# Respirador_Motor.net
KiCad netlist of a schematic drawn in EAGLE
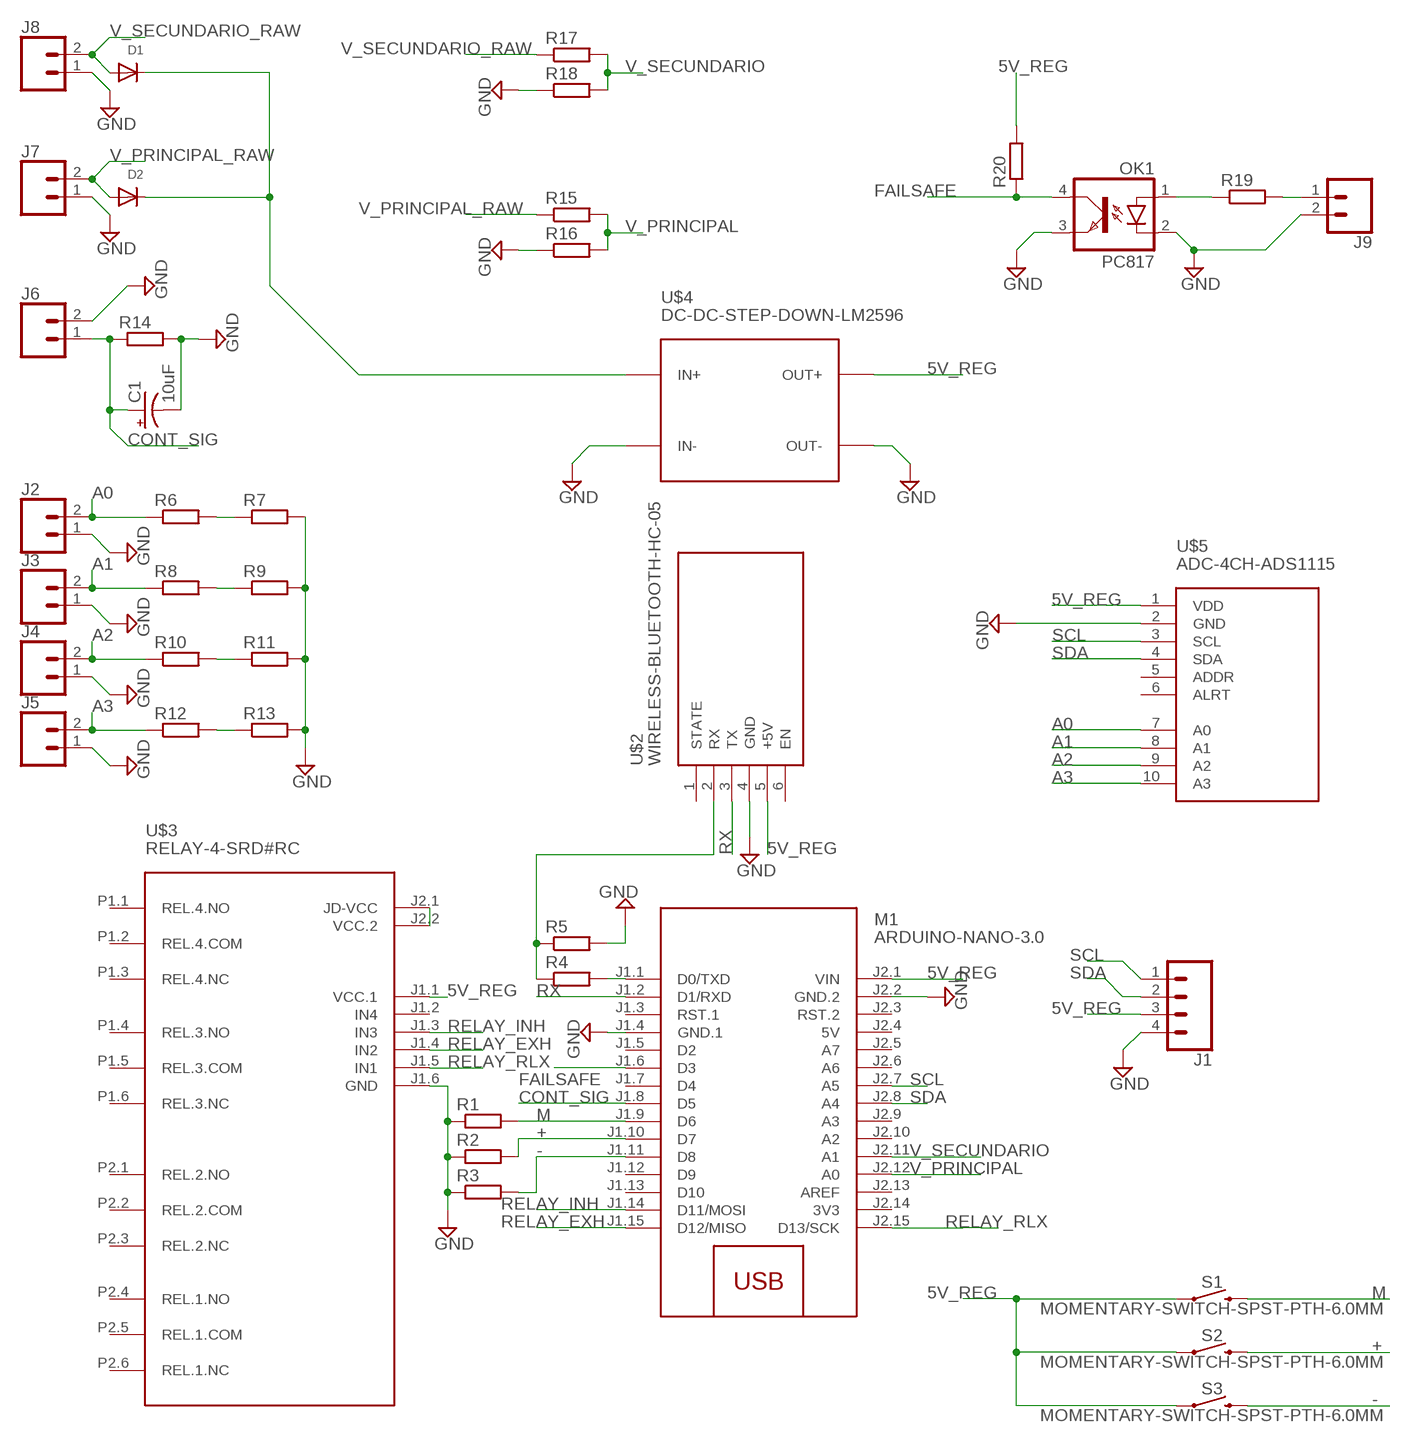
[diagram p0: schematic, sheet 1]

(export (version "E")
  (design (tool "Eeschema 10.0.6"))
  (components
    (comp (ref "C1")
      (value "10uF")
      (footprint "eagle-import:EIA3216")
      (libsource (lib "eagle-import") (part "10UF-TANT"))
    )
    (comp (ref "D1")
      (value "DIODEDO-1N4148")
      (footprint "eagle-import:DO-1N4148")
      (libsource (lib "eagle-import") (part "DIODEDO-1N4148"))
    )
    (comp (ref "D2")
      (value "DIODEDO-1N4148")
      (footprint "eagle-import:DO-1N4148")
      (libsource (lib "eagle-import") (part "DIODEDO-1N4148"))
    )
    (comp (ref "J1")
      (value "CONN_04")
      (footprint "eagle-import:1X04")
      (libsource (lib "eagle-import") (part "CONN_04"))
    )
    (comp (ref "J2")
      (value "CONN_025MM")
      (footprint "eagle-import:SCREWTERMINAL-5MM-2")
      (libsource (lib "eagle-import") (part "CONN_025MM"))
    )
    (comp (ref "J3")
      (value "CONN_025MM")
      (footprint "eagle-import:SCREWTERMINAL-5MM-2")
      (libsource (lib "eagle-import") (part "CONN_025MM"))
    )
    (comp (ref "J4")
      (value "CONN_025MM")
      (footprint "eagle-import:SCREWTERMINAL-5MM-2")
      (libsource (lib "eagle-import") (part "CONN_025MM"))
    )
    (comp (ref "J5")
      (value "CONN_025MM")
      (footprint "eagle-import:SCREWTERMINAL-5MM-2")
      (libsource (lib "eagle-import") (part "CONN_025MM"))
    )
    (comp (ref "J6")
      (value "CONN_025MM")
      (footprint "eagle-import:SCREWTERMINAL-5MM-2")
      (libsource (lib "eagle-import") (part "CONN_025MM"))
    )
    (comp (ref "J7")
      (value "CONN_025MM")
      (footprint "eagle-import:SCREWTERMINAL-5MM-2")
      (libsource (lib "eagle-import") (part "CONN_025MM"))
    )
    (comp (ref "J8")
      (value "CONN_025MM")
      (footprint "eagle-import:SCREWTERMINAL-5MM-2")
      (libsource (lib "eagle-import") (part "CONN_025MM"))
    )
    (comp (ref "J9")
      (value "CONN_025MM")
      (footprint "eagle-import:SCREWTERMINAL-5MM-2")
      (libsource (lib "eagle-import") (part "CONN_025MM"))
    )
    (comp (ref "M1")
      (value "ARDUINO-NANO-3.0")
      (footprint "eagle-import:ARDUINO-NANO-3.0")
      (libsource (lib "eagle-import") (part "ARDUINO-NANO-3.0"))
    )
    (comp (ref "OK1")
      (value "PC817")
      (footprint "eagle-import:DIL04")
      (fields (field (name "MPN") "PC817X4J000F"))
      (libsource (lib "eagle-import") (part "PC817"))
    )
    (comp (ref "R1")
      (value "R-EU_0207/10")
      (footprint "eagle-import:0207_10")
      (libsource (lib "eagle-import") (part "R-EU_0207/10"))
    )
    (comp (ref "R2")
      (value "R-EU_0207/10")
      (footprint "eagle-import:0207_10")
      (libsource (lib "eagle-import") (part "R-EU_0207/10"))
    )
    (comp (ref "R3")
      (value "R-EU_0207/10")
      (footprint "eagle-import:0207_10")
      (libsource (lib "eagle-import") (part "R-EU_0207/10"))
    )
    (comp (ref "R4")
      (value "R-EU_0207/10")
      (footprint "eagle-import:0207_10")
      (libsource (lib "eagle-import") (part "R-EU_0207/10"))
    )
    (comp (ref "R5")
      (value "R-EU_0207/10")
      (footprint "eagle-import:0207_10")
      (libsource (lib "eagle-import") (part "R-EU_0207/10"))
    )
    (comp (ref "R6")
      (value "R-EU_0207/10")
      (footprint "eagle-import:0207_10")
      (libsource (lib "eagle-import") (part "R-EU_0207/10"))
    )
    (comp (ref "R7")
      (value "R-EU_0207/10")
      (footprint "eagle-import:0207_10")
      (libsource (lib "eagle-import") (part "R-EU_0207/10"))
    )
    (comp (ref "R8")
      (value "R-EU_0207/10")
      (footprint "eagle-import:0207_10")
      (libsource (lib "eagle-import") (part "R-EU_0207/10"))
    )
    (comp (ref "R9")
      (value "R-EU_0207/10")
      (footprint "eagle-import:0207_10")
      (libsource (lib "eagle-import") (part "R-EU_0207/10"))
    )
    (comp (ref "R10")
      (value "R-EU_0207/10")
      (footprint "eagle-import:0207_10")
      (libsource (lib "eagle-import") (part "R-EU_0207/10"))
    )
    (comp (ref "R11")
      (value "R-EU_0207/10")
      (footprint "eagle-import:0207_10")
      (libsource (lib "eagle-import") (part "R-EU_0207/10"))
    )
    (comp (ref "R12")
      (value "R-EU_0207/10")
      (footprint "eagle-import:0207_10")
      (libsource (lib "eagle-import") (part "R-EU_0207/10"))
    )
    (comp (ref "R13")
      (value "R-EU_0207/10")
      (footprint "eagle-import:0207_10")
      (libsource (lib "eagle-import") (part "R-EU_0207/10"))
    )
    (comp (ref "R14")
      (value "R-EU_0207/10")
      (footprint "eagle-import:0207_10")
      (libsource (lib "eagle-import") (part "R-EU_0207/10"))
    )
    (comp (ref "R15")
      (value "R-EU_0207/10")
      (footprint "eagle-import:0207_10")
      (libsource (lib "eagle-import") (part "R-EU_0207/10"))
    )
    (comp (ref "R16")
      (value "R-EU_0207/10")
      (footprint "eagle-import:0207_10")
      (libsource (lib "eagle-import") (part "R-EU_0207/10"))
    )
    (comp (ref "R17")
      (value "R-EU_0207/10")
      (footprint "eagle-import:0207_10")
      (libsource (lib "eagle-import") (part "R-EU_0207/10"))
    )
    (comp (ref "R18")
      (value "R-EU_0207/10")
      (footprint "eagle-import:0207_10")
      (libsource (lib "eagle-import") (part "R-EU_0207/10"))
    )
    (comp (ref "R19")
      (value "R-EU_0207/10")
      (footprint "eagle-import:0207_10")
      (libsource (lib "eagle-import") (part "R-EU_0207/10"))
    )
    (comp (ref "R20")
      (value "R-EU_0207/10")
      (footprint "eagle-import:0207_10")
      (libsource (lib "eagle-import") (part "R-EU_0207/10"))
    )
    (comp (ref "S1")
      (value "MOMENTARY-SWITCH-SPST-PTH-6.0MM")
      (footprint "eagle-import:TACTILE_SWITCH_PTH_6.0MM")
      (libsource (lib "eagle-import") (part "MOMENTARY-SWITCH-SPST-PTH-6.0MM"))
    )
    (comp (ref "S2")
      (value "MOMENTARY-SWITCH-SPST-PTH-6.0MM")
      (footprint "eagle-import:TACTILE_SWITCH_PTH_6.0MM")
      (libsource (lib "eagle-import") (part "MOMENTARY-SWITCH-SPST-PTH-6.0MM"))
    )
    (comp (ref "S3")
      (value "MOMENTARY-SWITCH-SPST-PTH-6.0MM")
      (footprint "eagle-import:TACTILE_SWITCH_PTH_6.0MM")
      (libsource (lib "eagle-import") (part "MOMENTARY-SWITCH-SPST-PTH-6.0MM"))
    )
    (comp (ref "U$2")
      (value "WIRELESS-BLUETOOTH-HC-05")
      (footprint "eagle-import:WIRELESS-BLUETOOTH-HC-05")
      (libsource (lib "eagle-import") (part "WIRELESS-BLUETOOTH-HC-05"))
    )
    (comp (ref "U$3")
      (value "RELAY-4-SRD#RC")
      (footprint "eagle-import:RELAY-4-SRD#RC")
      (libsource (lib "eagle-import") (part "RELAY-4-SRD#RC"))
    )
    (comp (ref "U$4")
      (value "DC-DC-STEP-DOWN-LM2596")
      (footprint "eagle-import:DC-DC-STEP-DOWN-LM2596")
      (libsource (lib "eagle-import") (part "DC-DC-STEP-DOWN-LM2596"))
    )
    (comp (ref "U$5")
      (value "ADC-4CH-ADS1115")
      (footprint "eagle-import:ADC-4CH-ADS1115")
      (libsource (lib "eagle-import") (part "ADC-4CH-ADS1115"))
    )
  )
  (nets
    (net (code "1") (name "/+") (class "Default")
      (node (ref "M1") (pin "J1.10") (pinfunction "D7_J1.10") (pintype "bidirectional"))
      (node (ref "R2") (pin "2") (pinfunction "2_2") (pintype "passive"))
      (node (ref "S2") (pin "3") (pinfunction "2_3") (pintype "passive"))
    )
    (net (code "2") (name "/-") (class "Default")
      (node (ref "M1") (pin "J1.11") (pinfunction "D8_J1.11") (pintype "bidirectional"))
      (node (ref "R3") (pin "2") (pinfunction "2_2") (pintype "passive"))
      (node (ref "S3") (pin "3") (pinfunction "2_3") (pintype "passive"))
    )
    (net (code "3") (name "/3V3") (class "Default")
      (node (ref "M1") (pin "J2.14") (pinfunction "3V3_J2.14") (pintype "power_in"))
    )
    (net (code "4") (name "/5V") (class "Default")
      (node (ref "M1") (pin "J2.4") (pinfunction "5V_J2.4") (pintype "power_in"))
    )
    (net (code "5") (name "/5V_REG") (class "Default")
      (node (ref "J1") (pin "3") (pinfunction "3_3") (pintype "passive"))
      (node (ref "M1") (pin "J2.1") (pinfunction "VIN_J2.1") (pintype "power_in"))
      (node (ref "R20") (pin "2") (pinfunction "2_2") (pintype "passive"))
      (node (ref "S1") (pin "1") (pinfunction "1_1") (pintype "passive"))
      (node (ref "S2") (pin "1") (pinfunction "1_1") (pintype "passive"))
      (node (ref "S3") (pin "1") (pinfunction "1_1") (pintype "passive"))
      (node (ref "U$2") (pin "5") (pinfunction "+5V_5") (pintype "power_in"))
      (node (ref "U$3") (pin "J1.1") (pinfunction "VCC.1_J1.1") (pintype "power_in"))
      (node (ref "U$4") (pin "OUT+") (pinfunction "OUT+_OUT+") (pintype "bidirectional"))
      (node (ref "U$5") (pin "1") (pinfunction "VDD_1") (pintype "power_in"))
    )
    (net (code "6") (name "/A0") (class "Default")
      (node (ref "J2") (pin "2") (pinfunction "2_2") (pintype "passive"))
      (node (ref "R6") (pin "1") (pinfunction "1_1") (pintype "passive"))
      (node (ref "U$5") (pin "7") (pinfunction "A0_7") (pintype "input"))
    )
    (net (code "7") (name "/A1") (class "Default")
      (node (ref "J3") (pin "2") (pinfunction "2_2") (pintype "passive"))
      (node (ref "R8") (pin "1") (pinfunction "1_1") (pintype "passive"))
      (node (ref "U$5") (pin "8") (pinfunction "A1_8") (pintype "input"))
    )
    (net (code "8") (name "/A2") (class "Default")
      (node (ref "J4") (pin "2") (pinfunction "2_2") (pintype "passive"))
      (node (ref "R10") (pin "1") (pinfunction "1_1") (pintype "passive"))
      (node (ref "U$5") (pin "9") (pinfunction "A2_9") (pintype "input"))
    )
    (net (code "9") (name "/A3") (class "Default")
      (node (ref "J5") (pin "2") (pinfunction "2_2") (pintype "passive"))
      (node (ref "R12") (pin "1") (pinfunction "1_1") (pintype "passive"))
      (node (ref "U$5") (pin "10") (pinfunction "A3_10") (pintype "input"))
    )
    (net (code "10") (name "/CONT_SIG") (class "Default")
      (node (ref "C1") (pin "A") (pinfunction "+_A") (pintype "passive"))
      (node (ref "J6") (pin "1") (pinfunction "1_1") (pintype "passive"))
      (node (ref "M1") (pin "J1.8") (pinfunction "D5_J1.8") (pintype "bidirectional"))
      (node (ref "R14") (pin "1") (pinfunction "1_1") (pintype "passive"))
    )
    (net (code "11") (name "/FAILSAFE") (class "Default")
      (node (ref "M1") (pin "J1.6") (pinfunction "D3_J1.6") (pintype "bidirectional"))
      (node (ref "OK1") (pin "4") (pinfunction "COL_4") (pintype "passive"))
      (node (ref "R20") (pin "1") (pinfunction "1_1") (pintype "passive"))
    )
    (net (code "12") (name "/M") (class "Default")
      (node (ref "M1") (pin "J1.9") (pinfunction "D6_J1.9") (pintype "bidirectional"))
      (node (ref "R1") (pin "2") (pinfunction "2_2") (pintype "passive"))
      (node (ref "S1") (pin "3") (pinfunction "2_3") (pintype "passive"))
    )
    (net (code "13") (name "/RELAY_EXH") (class "Default")
      (node (ref "M1") (pin "J1.15") (pinfunction "D12/MISO_J1.15") (pintype "bidirectional"))
      (node (ref "U$3") (pin "J1.4") (pinfunction "IN2_J1.4") (pintype "bidirectional"))
    )
    (net (code "14") (name "/RELAY_INH") (class "Default")
      (node (ref "M1") (pin "J1.14") (pinfunction "D11/MOSI_J1.14") (pintype "bidirectional"))
      (node (ref "U$3") (pin "J1.3") (pinfunction "IN3_J1.3") (pintype "bidirectional"))
    )
    (net (code "15") (name "/RELAY_RLX") (class "Default")
      (node (ref "M1") (pin "J2.15") (pinfunction "D13/SCK_J2.15") (pintype "bidirectional"))
      (node (ref "U$3") (pin "J1.5") (pinfunction "IN1_J1.5") (pintype "bidirectional"))
    )
    (net (code "16") (name "/RX") (class "Default")
      (node (ref "M1") (pin "J1.2") (pinfunction "D1/RXD_J1.2") (pintype "bidirectional"))
      (node (ref "U$2") (pin "3") (pinfunction "TX_3") (pintype "bidirectional"))
    )
    (net (code "17") (name "/SCL") (class "Default")
      (node (ref "J1") (pin "1") (pinfunction "1_1") (pintype "passive"))
      (node (ref "M1") (pin "J2.7") (pinfunction "A5_J2.7") (pintype "bidirectional"))
      (node (ref "U$5") (pin "3") (pinfunction "SCL_3") (pintype "bidirectional"))
    )
    (net (code "18") (name "/SDA") (class "Default")
      (node (ref "J1") (pin "2") (pinfunction "2_2") (pintype "passive"))
      (node (ref "M1") (pin "J2.8") (pinfunction "A4_J2.8") (pintype "bidirectional"))
      (node (ref "U$5") (pin "4") (pinfunction "SDA_4") (pintype "bidirectional"))
    )
    (net (code "19") (name "/V_PRINCIPAL") (class "Default")
      (node (ref "M1") (pin "J2.12") (pinfunction "A0_J2.12") (pintype "bidirectional"))
      (node (ref "R15") (pin "2") (pinfunction "2_2") (pintype "passive"))
      (node (ref "R16") (pin "2") (pinfunction "2_2") (pintype "passive"))
    )
    (net (code "20") (name "/V_PRINCIPAL_RAW") (class "Default")
      (node (ref "D2") (pin "A") (pinfunction "A_A") (pintype "passive"))
      (node (ref "J7") (pin "2") (pinfunction "2_2") (pintype "passive"))
      (node (ref "R15") (pin "1") (pinfunction "1_1") (pintype "passive"))
    )
    (net (code "21") (name "/V_SECUNDARIO") (class "Default")
      (node (ref "M1") (pin "J2.11") (pinfunction "A1_J2.11") (pintype "bidirectional"))
      (node (ref "R17") (pin "2") (pinfunction "2_2") (pintype "passive"))
      (node (ref "R18") (pin "2") (pinfunction "2_2") (pintype "passive"))
    )
    (net (code "22") (name "/V_SECUNDARIO_RAW") (class "Default")
      (node (ref "D1") (pin "A") (pinfunction "A_A") (pintype "passive"))
      (node (ref "J8") (pin "2") (pinfunction "2_2") (pintype "passive"))
      (node (ref "R17") (pin "1") (pinfunction "1_1") (pintype "passive"))
    )
    (net (code "23") (name "GND") (class "Default")
      (node (ref "C1") (pin "C") (pinfunction "-_C") (pintype "passive"))
      (node (ref "J1") (pin "4") (pinfunction "4_4") (pintype "passive"))
      (node (ref "J2") (pin "1") (pinfunction "1_1") (pintype "passive"))
      (node (ref "J3") (pin "1") (pinfunction "1_1") (pintype "passive"))
      (node (ref "J4") (pin "1") (pinfunction "1_1") (pintype "passive"))
      (node (ref "J5") (pin "1") (pinfunction "1_1") (pintype "passive"))
      (node (ref "J6") (pin "2") (pinfunction "2_2") (pintype "passive"))
      (node (ref "J7") (pin "1") (pinfunction "1_1") (pintype "passive"))
      (node (ref "J8") (pin "1") (pinfunction "1_1") (pintype "passive"))
      (node (ref "J9") (pin "2") (pinfunction "2_2") (pintype "passive"))
      (node (ref "M1") (pin "J1.4") (pinfunction "GND.1_J1.4") (pintype "power_in"))
      (node (ref "M1") (pin "J2.2") (pinfunction "GND.2_J2.2") (pintype "power_in"))
      (node (ref "OK1") (pin "2") (pinfunction "C_2") (pintype "passive"))
      (node (ref "OK1") (pin "3") (pinfunction "EMIT_3") (pintype "passive"))
      (node (ref "R1") (pin "1") (pinfunction "1_1") (pintype "passive"))
      (node (ref "R11") (pin "2") (pinfunction "2_2") (pintype "passive"))
      (node (ref "R13") (pin "2") (pinfunction "2_2") (pintype "passive"))
      (node (ref "R14") (pin "2") (pinfunction "2_2") (pintype "passive"))
      (node (ref "R16") (pin "1") (pinfunction "1_1") (pintype "passive"))
      (node (ref "R18") (pin "1") (pinfunction "1_1") (pintype "passive"))
      (node (ref "R2") (pin "1") (pinfunction "1_1") (pintype "passive"))
      (node (ref "R3") (pin "1") (pinfunction "1_1") (pintype "passive"))
      (node (ref "R5") (pin "2") (pinfunction "2_2") (pintype "passive"))
      (node (ref "R7") (pin "2") (pinfunction "2_2") (pintype "passive"))
      (node (ref "R9") (pin "2") (pinfunction "2_2") (pintype "passive"))
      (node (ref "U$2") (pin "4") (pinfunction "GND_4") (pintype "power_in"))
      (node (ref "U$3") (pin "J1.6") (pinfunction "GND_J1.6") (pintype "power_in"))
      (node (ref "U$4") (pin "IN-") (pinfunction "IN-_IN-") (pintype "bidirectional"))
      (node (ref "U$4") (pin "OUT-") (pinfunction "OUT-_OUT-") (pintype "bidirectional"))
      (node (ref "U$5") (pin "2") (pinfunction "GND_2") (pintype "power_in"))
    )
    (net (code "24") (name "Net-(D1-PadC)") (class "Default")
      (node (ref "D1") (pin "C") (pinfunction "C_C") (pintype "passive"))
      (node (ref "D2") (pin "C") (pinfunction "C_C") (pintype "passive"))
      (node (ref "U$4") (pin "IN+") (pinfunction "IN+_IN+") (pintype "bidirectional"))
    )
    (net (code "25") (name "Net-(J9-Pad1)") (class "Default")
      (node (ref "J9") (pin "1") (pinfunction "1_1") (pintype "passive"))
      (node (ref "R19") (pin "2") (pinfunction "2_2") (pintype "passive"))
    )
    (net (code "26") (name "Net-(M1-D0{slash}TXD)") (class "Default")
      (node (ref "M1") (pin "J1.1") (pinfunction "D0/TXD_J1.1") (pintype "bidirectional"))
      (node (ref "R4") (pin "2") (pinfunction "2_2") (pintype "passive"))
    )
    (net (code "27") (name "Net-(OK1-A)") (class "Default")
      (node (ref "OK1") (pin "1") (pinfunction "A_1") (pintype "passive"))
      (node (ref "R19") (pin "1") (pinfunction "1_1") (pintype "passive"))
    )
    (net (code "28") (name "Net-(R6-Pad2)") (class "Default")
      (node (ref "R6") (pin "2") (pinfunction "2_2") (pintype "passive"))
      (node (ref "R7") (pin "1") (pinfunction "1_1") (pintype "passive"))
    )
    (net (code "29") (name "Net-(R8-Pad2)") (class "Default")
      (node (ref "R8") (pin "2") (pinfunction "2_2") (pintype "passive"))
      (node (ref "R9") (pin "1") (pinfunction "1_1") (pintype "passive"))
    )
    (net (code "30") (name "Net-(R10-Pad2)") (class "Default")
      (node (ref "R10") (pin "2") (pinfunction "2_2") (pintype "passive"))
      (node (ref "R11") (pin "1") (pinfunction "1_1") (pintype "passive"))
    )
    (net (code "31") (name "Net-(R12-Pad2)") (class "Default")
      (node (ref "R12") (pin "2") (pinfunction "2_2") (pintype "passive"))
      (node (ref "R13") (pin "1") (pinfunction "1_1") (pintype "passive"))
    )
    (net (code "32") (name "Net-(U$2-RX)") (class "Default")
      (node (ref "R4") (pin "1") (pinfunction "1_1") (pintype "passive"))
      (node (ref "R5") (pin "1") (pinfunction "1_1") (pintype "passive"))
      (node (ref "U$2") (pin "2") (pinfunction "RX_2") (pintype "bidirectional"))
    )
    (net (code "33") (name "Net-(U$3-JD-VCC)") (class "Default")
      (node (ref "U$3") (pin "J2.1") (pinfunction "JD-VCC_J2.1") (pintype "bidirectional"))
      (node (ref "U$3") (pin "J2.2") (pinfunction "VCC.2_J2.2") (pintype "power_in"))
    )
    (net (code "34") (name "unconnected-(M1-A2-PadJ2.10)") (class "Default")
      (node (ref "M1") (pin "J2.10") (pinfunction "A2_J2.10") (pintype "bidirectional"))
    )
    (net (code "35") (name "unconnected-(M1-A3-PadJ2.9)") (class "Default")
      (node (ref "M1") (pin "J2.9") (pinfunction "A3_J2.9") (pintype "bidirectional"))
    )
    (net (code "36") (name "unconnected-(M1-A6-PadJ2.6)") (class "Default")
      (node (ref "M1") (pin "J2.6") (pinfunction "A6_J2.6") (pintype "bidirectional"))
    )
    (net (code "37") (name "unconnected-(M1-A7-PadJ2.5)") (class "Default")
      (node (ref "M1") (pin "J2.5") (pinfunction "A7_J2.5") (pintype "bidirectional"))
    )
    (net (code "38") (name "unconnected-(M1-AREF-PadJ2.13)") (class "Default")
      (node (ref "M1") (pin "J2.13") (pinfunction "AREF_J2.13") (pintype "bidirectional"))
    )
    (net (code "39") (name "unconnected-(M1-D2-PadJ1.5)") (class "Default")
      (node (ref "M1") (pin "J1.5") (pinfunction "D2_J1.5") (pintype "bidirectional"))
    )
    (net (code "40") (name "unconnected-(M1-D4-PadJ1.7)") (class "Default")
      (node (ref "M1") (pin "J1.7") (pinfunction "D4_J1.7") (pintype "bidirectional"))
    )
    (net (code "41") (name "unconnected-(M1-D9-PadJ1.12)") (class "Default")
      (node (ref "M1") (pin "J1.12") (pinfunction "D9_J1.12") (pintype "bidirectional"))
    )
    (net (code "42") (name "unconnected-(M1-D10-PadJ1.13)") (class "Default")
      (node (ref "M1") (pin "J1.13") (pinfunction "D10_J1.13") (pintype "bidirectional"))
    )
    (net (code "43") (name "unconnected-(M1-RST.1-PadJ1.3)") (class "Default")
      (node (ref "M1") (pin "J1.3") (pinfunction "RST.1_J1.3") (pintype "bidirectional"))
    )
    (net (code "44") (name "unconnected-(M1-RST.2-PadJ2.3)") (class "Default")
      (node (ref "M1") (pin "J2.3") (pinfunction "RST.2_J2.3") (pintype "bidirectional"))
    )
    (net (code "45") (name "unconnected-(U$2-EN-Pad6)") (class "Default")
      (node (ref "U$2") (pin "6") (pinfunction "EN_6") (pintype "bidirectional"))
    )
    (net (code "46") (name "unconnected-(U$2-STATE-Pad1)") (class "Default")
      (node (ref "U$2") (pin "1") (pinfunction "STATE_1") (pintype "bidirectional"))
    )
    (net (code "47") (name "unconnected-(U$3-IN4-PadJ1.2)") (class "Default")
      (node (ref "U$3") (pin "J1.2") (pinfunction "IN4_J1.2") (pintype "bidirectional"))
    )
    (net (code "48") (name "unconnected-(U$3-REL.1.COM-PadP2.5)") (class "Default")
      (node (ref "U$3") (pin "P2.5") (pinfunction "REL.1.COM_P2.5") (pintype "bidirectional"))
    )
    (net (code "49") (name "unconnected-(U$3-REL.1.NC-PadP2.6)") (class "Default")
      (node (ref "U$3") (pin "P2.6") (pinfunction "REL.1.NC_P2.6") (pintype "bidirectional"))
    )
    (net (code "50") (name "unconnected-(U$3-REL.1.NO-PadP2.4)") (class "Default")
      (node (ref "U$3") (pin "P2.4") (pinfunction "REL.1.NO_P2.4") (pintype "bidirectional"))
    )
    (net (code "51") (name "unconnected-(U$3-REL.2.COM-PadP2.2)") (class "Default")
      (node (ref "U$3") (pin "P2.2") (pinfunction "REL.2.COM_P2.2") (pintype "bidirectional"))
    )
    (net (code "52") (name "unconnected-(U$3-REL.2.NC-PadP2.3)") (class "Default")
      (node (ref "U$3") (pin "P2.3") (pinfunction "REL.2.NC_P2.3") (pintype "bidirectional"))
    )
    (net (code "53") (name "unconnected-(U$3-REL.2.NO-PadP2.1)") (class "Default")
      (node (ref "U$3") (pin "P2.1") (pinfunction "REL.2.NO_P2.1") (pintype "bidirectional"))
    )
    (net (code "54") (name "unconnected-(U$3-REL.3.COM-PadP1.5)") (class "Default")
      (node (ref "U$3") (pin "P1.5") (pinfunction "REL.3.COM_P1.5") (pintype "bidirectional"))
    )
    (net (code "55") (name "unconnected-(U$3-REL.3.NC-PadP1.6)") (class "Default")
      (node (ref "U$3") (pin "P1.6") (pinfunction "REL.3.NC_P1.6") (pintype "bidirectional"))
    )
    (net (code "56") (name "unconnected-(U$3-REL.3.NO-PadP1.4)") (class "Default")
      (node (ref "U$3") (pin "P1.4") (pinfunction "REL.3.NO_P1.4") (pintype "bidirectional"))
    )
    (net (code "57") (name "unconnected-(U$3-REL.4.COM-PadP1.2)") (class "Default")
      (node (ref "U$3") (pin "P1.2") (pinfunction "REL.4.COM_P1.2") (pintype "bidirectional"))
    )
    (net (code "58") (name "unconnected-(U$3-REL.4.NC-PadP1.3)") (class "Default")
      (node (ref "U$3") (pin "P1.3") (pinfunction "REL.4.NC_P1.3") (pintype "bidirectional"))
    )
    (net (code "59") (name "unconnected-(U$3-REL.4.NO-PadP1.1)") (class "Default")
      (node (ref "U$3") (pin "P1.1") (pinfunction "REL.4.NO_P1.1") (pintype "bidirectional"))
    )
    (net (code "60") (name "unconnected-(U$5-ADDR-Pad5)") (class "Default")
      (node (ref "U$5") (pin "5") (pinfunction "ADDR_5") (pintype "bidirectional"))
    )
    (net (code "61") (name "unconnected-(U$5-ALRT-Pad6)") (class "Default")
      (node (ref "U$5") (pin "6") (pinfunction "ALRT_6") (pintype "bidirectional"))
    )
  )
)
